# 4Wheel_MotorDrivers_Encoders.net
KiCad netlist of a schematic drawn in Altium Designer
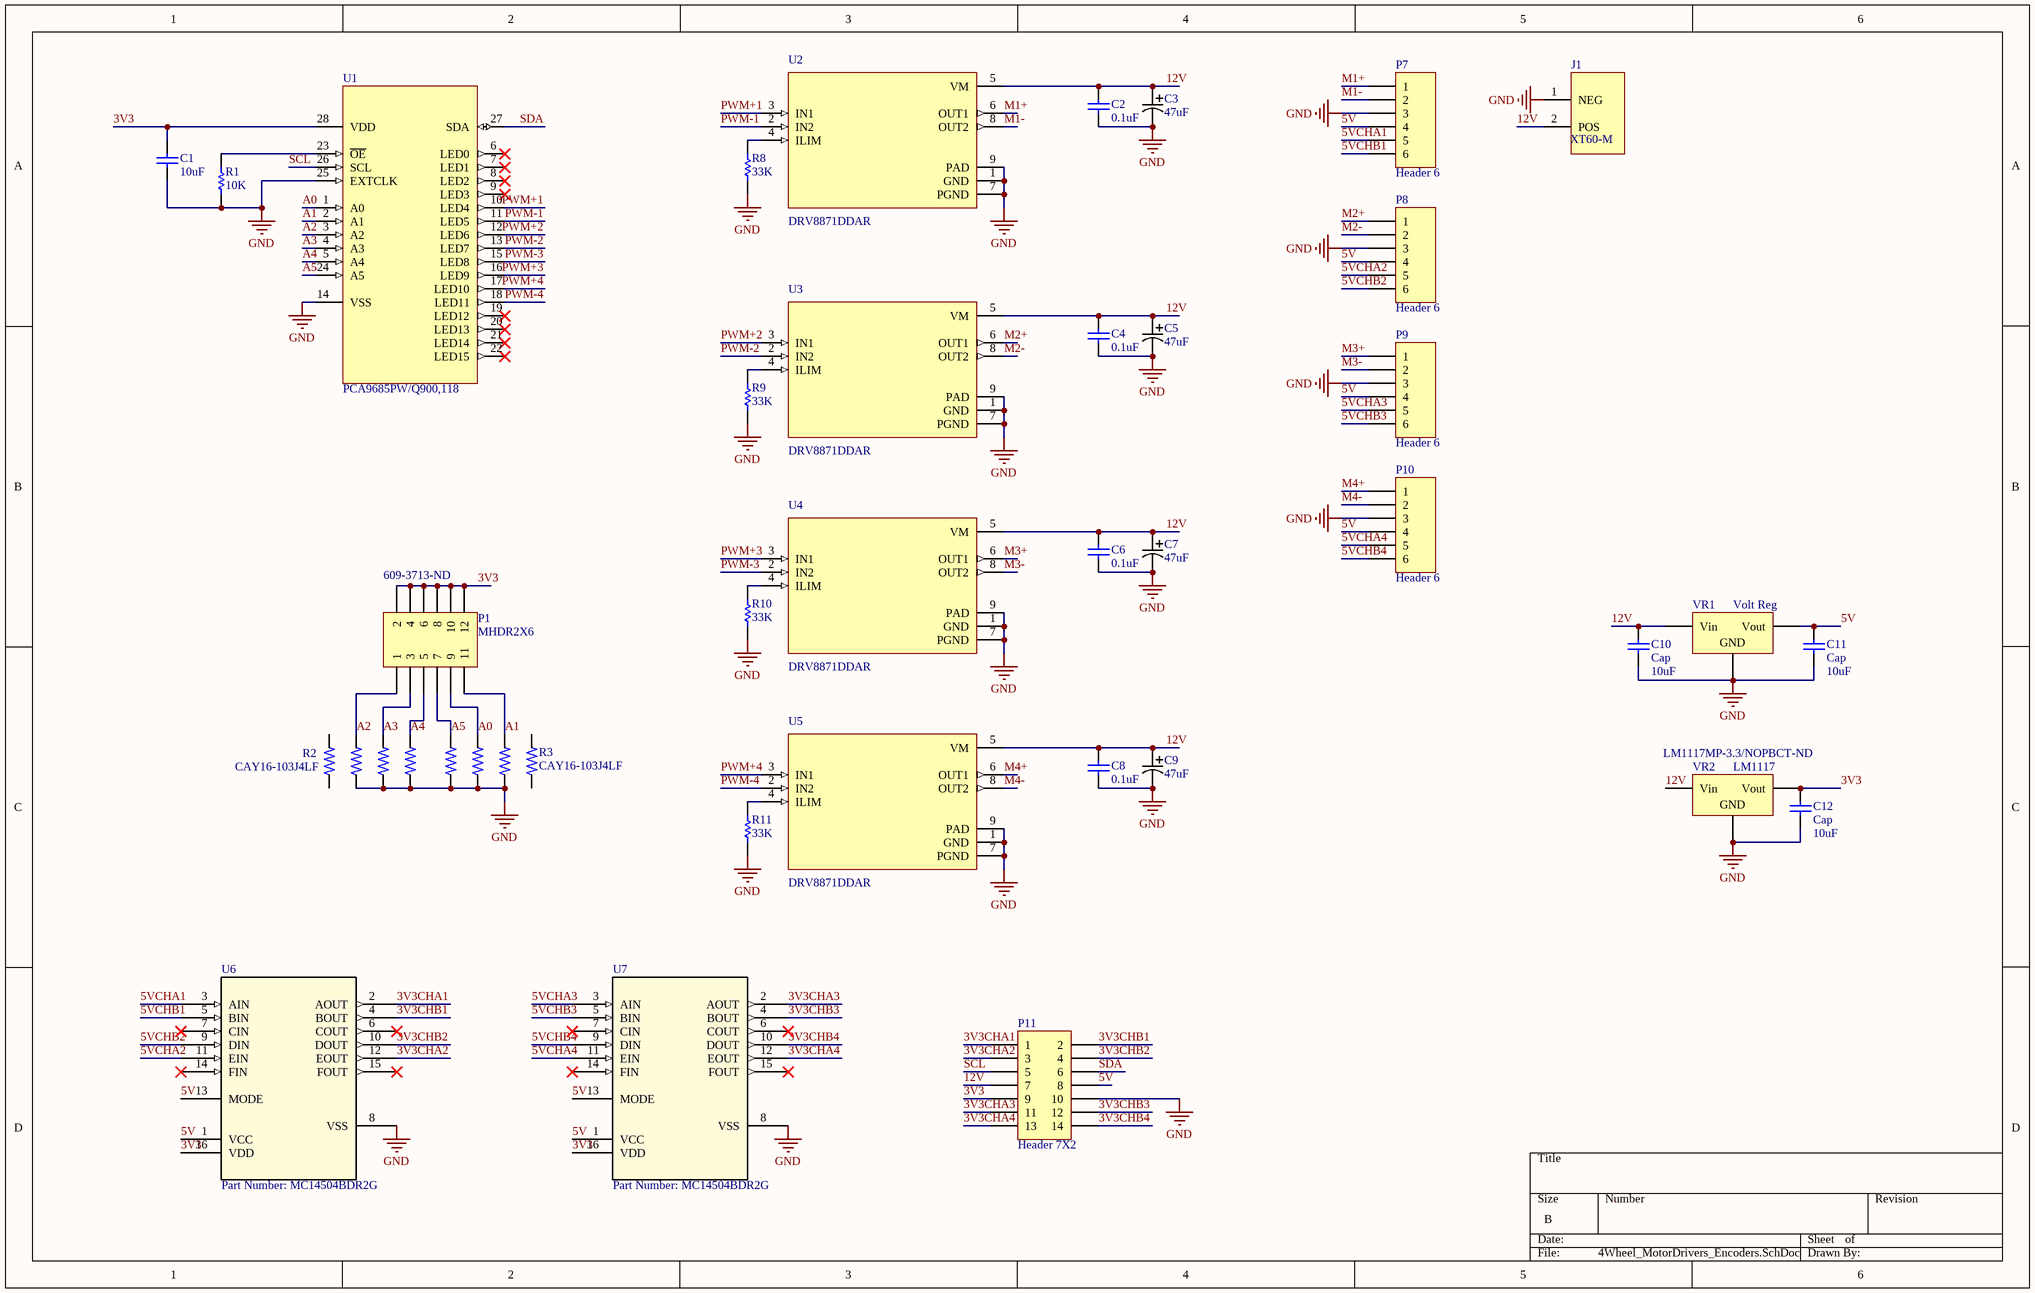
[diagram p0: 4Wheel_MotorDrivers_Encoders.SchDoc]

(export (version "E")
  (design (tool "Eeschema 10.0.6"))
  (components
    (comp (ref "C1")
      (value "10uF")
      (footprint "6-0805_N")
      (description "Capacitor")
      (fields (field (name "Comment") "Cap") (field (name "PUBLISHER") "Altium Limited"))
      (libsource (lib "Miscellaneous Devices") (part "Cap"))
    )
    (comp (ref "C2")
      (value "0.1uF")
      (footprint "6-0805_N")
      (description "Capacitor")
      (fields (field (name "PUBLISHER") "Altium Limited"))
      (libsource (lib "Miscellaneous Devices") (part "Cap"))
    )
    (comp (ref "C3")
      (value "47uF")
      (footprint "PCAP_6.3x7.7-ELE")
      (description "No Description Available")
      (fields
        (field (name "MANUFACTURER_PART_NUMBER") "UWT1H470MCL1GS")
        (field (name "COPYRIGHT") "Copyright (C) 2018 Accelerated Designs. All rights reserved")
      )
      (libsource (lib "2020-02-13_23-38-10") (part "UWT1H470MCL1GS"))
    )
    (comp (ref "C4")
      (value "0.1uF")
      (footprint "6-0805_N")
      (description "Capacitor")
      (fields (field (name "PUBLISHER") "Altium Limited"))
      (libsource (lib "Miscellaneous Devices") (part "Cap"))
    )
    (comp (ref "C5")
      (value "47uF")
      (footprint "PCAP_6.3x7.7-ELE")
      (description "No Description Available")
      (fields
        (field (name "MANUFACTURER_PART_NUMBER") "UWT1H470MCL1GS")
        (field (name "COPYRIGHT") "Copyright (C) 2018 Accelerated Designs. All rights reserved")
      )
      (libsource (lib "2020-02-13_23-38-10") (part "UWT1H470MCL1GS"))
    )
    (comp (ref "C6")
      (value "0.1uF")
      (footprint "6-0805_N")
      (description "Capacitor")
      (fields (field (name "PUBLISHER") "Altium Limited"))
      (libsource (lib "Miscellaneous Devices") (part "Cap"))
    )
    (comp (ref "C7")
      (value "47uF")
      (footprint "PCAP_6.3x7.7-ELE")
      (description "No Description Available")
      (fields
        (field (name "MANUFACTURER_PART_NUMBER") "UWT1H470MCL1GS")
        (field (name "COPYRIGHT") "Copyright (C) 2018 Accelerated Designs. All rights reserved")
      )
      (libsource (lib "2020-02-13_23-38-10") (part "UWT1H470MCL1GS"))
    )
    (comp (ref "C8")
      (value "0.1uF")
      (footprint "6-0805_N")
      (description "Capacitor")
      (fields (field (name "PUBLISHER") "Altium Limited"))
      (libsource (lib "Miscellaneous Devices") (part "Cap"))
    )
    (comp (ref "C9")
      (value "47uF")
      (footprint "PCAP_6.3x7.7-ELE")
      (description "No Description Available")
      (fields
        (field (name "MANUFACTURER_PART_NUMBER") "UWT1H470MCL1GS")
        (field (name "COPYRIGHT") "Copyright (C) 2018 Accelerated Designs. All rights reserved")
      )
      (libsource (lib "2020-02-13_23-38-10") (part "UWT1H470MCL1GS"))
    )
    (comp (ref "C10")
      (value "Cap")
      (footprint "6-0805_N")
      (description "Capacitor")
      (fields (field (name "ALTIUM_VALUE") "10uF") (field (name "PUBLISHER") "Altium Limited"))
      (libsource (lib "Miscellaneous Devices") (part "Cap"))
    )
    (comp (ref "C11")
      (value "Cap")
      (footprint "6-0805_N")
      (description "Capacitor")
      (fields (field (name "ALTIUM_VALUE") "10uF") (field (name "PUBLISHER") "Altium Limited"))
      (libsource (lib "Miscellaneous Devices") (part "Cap"))
    )
    (comp (ref "C12")
      (value "Cap")
      (footprint "6-0805_N")
      (description "Capacitor")
      (fields (field (name "ALTIUM_VALUE") "10uF") (field (name "PUBLISHER") "Altium Limited"))
      (libsource (lib "Miscellaneous Devices") (part "Cap"))
    )
    (comp (ref "J1")
      (value "XT60-M")
      (footprint "*AMASS_XT60-M")
      (description "Plug; DC supply; XT60; male; PIN: 2; for cable; soldered; 30A; 500V")
      (fields (field (name "MF") "AMASS"))
      (libsource (lib "XT60-M") (part "XT60-M"))
    )
    (comp (ref "P1")
      (value "MHDR2X6")
      (footprint "MHDR2X6")
      (description "Header, 6-Pin, Dual row")
      (fields
        (field (name "SUPPLIER PART NUMBER 1") "609-3713-ND")
        (field (name "PUBLISHER") "Altium Limited")
      )
      (libsource (lib "Miscellaneous Connectors") (part "MHDR2X6"))
    )
    (comp (ref "P7")
      (value "Header 6")
      (footprint "HDR1X6")
      (description "Header, 6-Pin")
      (fields (field (name "PUBLISHER") "Altium Limited"))
      (libsource (lib "Miscellaneous Connectors") (part "Header 6"))
    )
    (comp (ref "P8")
      (value "Header 6")
      (footprint "HDR1X6")
      (description "Header, 6-Pin")
      (fields (field (name "PUBLISHER") "Altium Limited"))
      (libsource (lib "Miscellaneous Connectors") (part "Header 6"))
    )
    (comp (ref "P9")
      (value "Header 6")
      (footprint "HDR1X6")
      (description "Header, 6-Pin")
      (fields (field (name "PUBLISHER") "Altium Limited"))
      (libsource (lib "Miscellaneous Connectors") (part "Header 6"))
    )
    (comp (ref "P10")
      (value "Header 6")
      (footprint "HDR1X6")
      (description "Header, 6-Pin")
      (fields (field (name "PUBLISHER") "Altium Limited"))
      (libsource (lib "Miscellaneous Connectors") (part "Header 6"))
    )
    (comp (ref "P11")
      (value "Header 7X2")
      (footprint "HDR1X14")
      (description "Header, 7-Pin, Dual row")
      (fields (field (name "PUBLISHER") "Altium Limited"))
      (libsource (lib "Miscellaneous Connectors") (part "Header 7X2"))
    )
    (comp (ref "R1")
      (value "10K")
      (footprint "6-0805_N")
      (description "Resistor")
      (fields (field (name "Comment") "Res1") (field (name "PUBLISHER") "Altium Limited"))
      (libsource (lib "Miscellaneous Devices") (part "Res1"))
    )
    (comp (ref "R2")
      (value "CAY16-103J4LF")
      (footprint "CAY16-J4")
      (fields (field (name "MF") "Bourns"))
      (libsource (lib "CAY16-103J4LF") (part "CAY16-103J4LF"))
    )
    (comp (ref "R3")
      (value "CAY16-103J4LF")
      (footprint "CAY16-J4")
      (fields (field (name "MF") "Bourns"))
      (libsource (lib "CAY16-103J4LF") (part "CAY16-103J4LF"))
    )
    (comp (ref "R8")
      (value "33K")
      (footprint "6-0805_N")
      (description "Resistor")
      (fields (field (name "Comment") "Res1") (field (name "PUBLISHER") "Altium Limited"))
      (libsource (lib "Miscellaneous Devices") (part "Res1"))
    )
    (comp (ref "R9")
      (value "33K")
      (footprint "6-0805_N")
      (description "Resistor")
      (fields (field (name "Comment") "Res1") (field (name "PUBLISHER") "Altium Limited"))
      (libsource (lib "Miscellaneous Devices") (part "Res1"))
    )
    (comp (ref "R10")
      (value "33K")
      (footprint "6-0805_N")
      (description "Resistor")
      (fields (field (name "Comment") "Res1") (field (name "PUBLISHER") "Altium Limited"))
      (libsource (lib "Miscellaneous Devices") (part "Res1"))
    )
    (comp (ref "R11")
      (value "33K")
      (footprint "6-0805_N")
      (description "Resistor")
      (fields (field (name "Comment") "Res1") (field (name "PUBLISHER") "Altium Limited"))
      (libsource (lib "Miscellaneous Devices") (part "Res1"))
    )
    (comp (ref "U1")
      (value "PCA9685PW/Q900,118")
      (footprint "*SOP65P640X110-28N")
      (description "LED Driver IC 16 Output Linear PWM Dimming 25mA 28-TSSOP")
      (fields (field (name "MF") "NXP USA") (field (name "DIGI-KEY_PART_NUMBER") "568-5931-1-ND"))
      (libsource (lib "PCA9685PW_Q900_118") (part "PCA9685PW/Q900,118"))
    )
    (comp (ref "U2")
      (value "DRV8871DDAR")
      (footprint "*SOIC127P600X170-8N")
      (description "Unipolar Motor Driver NMOS PWM 8-SO PowerPad")
      (fields (field (name "DIGI-KEY_PART_NUMBER") "296-43024-1-ND") (field (name "MF") "Texas Instruments"))
      (libsource (lib "DRV8871DDAR") (part "DRV8871DDAR"))
    )
    (comp (ref "U3")
      (value "DRV8871DDAR")
      (footprint "*SOIC127P600X170-8N")
      (description "Unipolar Motor Driver NMOS PWM 8-SO PowerPad")
      (fields (field (name "DIGI-KEY_PART_NUMBER") "296-43024-1-ND") (field (name "MF") "Texas Instruments"))
      (libsource (lib "DRV8871DDAR") (part "DRV8871DDAR"))
    )
    (comp (ref "U4")
      (value "DRV8871DDAR")
      (footprint "*SOIC127P600X170-8N")
      (description "Unipolar Motor Driver NMOS PWM 8-SO PowerPad")
      (fields (field (name "DIGI-KEY_PART_NUMBER") "296-43024-1-ND") (field (name "MF") "Texas Instruments"))
      (libsource (lib "DRV8871DDAR") (part "DRV8871DDAR"))
    )
    (comp (ref "U5")
      (value "DRV8871DDAR")
      (footprint "*SOIC127P600X170-8N")
      (description "Unipolar Motor Driver NMOS PWM 8-SO PowerPad")
      (fields (field (name "DIGI-KEY_PART_NUMBER") "296-43024-1-ND") (field (name "MF") "Texas Instruments"))
      (libsource (lib "DRV8871DDAR") (part "DRV8871DDAR"))
    )
    (comp (ref "U6")
      (value "Part Number: MC14504BDR2G")
      (footprint "SOIC-16")
      (description "No Description Available")
      (fields
        (field (name "MANUFACTURER_PART_NUMBER") "MC14504BDR2G")
        (field (name "COPYRIGHT") "Copyright (C) 2016 Accelerated Designs. All rights reserved")
      )
      (libsource (lib "2020-02-13_23-03-03") (part "MC14504BDR2G"))
    )
    (comp (ref "U7")
      (value "Part Number: MC14504BDR2G")
      (footprint "SOIC-16")
      (description "No Description Available")
      (fields
        (field (name "MANUFACTURER_PART_NUMBER") "MC14504BDR2G")
        (field (name "COPYRIGHT") "Copyright (C) 2016 Accelerated Designs. All rights reserved")
      )
      (libsource (lib "2020-02-13_23-03-03") (part "MC14504BDR2G"))
    )
    (comp (ref "VR1")
      (value "Volt Reg")
      (footprint "*TO254P1524X483-4N")
      (description "Voltage Regulator")
      (fields (field (name "PUBLISHER") "Altium Limited"))
      (libsource (lib "Miscellaneous Devices") (part "Volt Reg"))
    )
    (comp (ref "VR2")
      (value "LM1117")
      (footprint "SOT223_L")
      (description "Voltage Regulator")
      (fields
        (field (name "SUPPLIER PART NUMBER 1") "LM1117MP-3.3/NOPBCT-ND")
        (field (name "PUBLISHER") "Altium Limited")
      )
      (libsource (lib "Miscellaneous Devices") (part "Volt Reg"))
    )
  )
  (nets
    (net (code "1") (name "/3V3") (class "Default")
      (node (ref "C1") (pin "2") (pinfunction "2_2") (pintype "passive"))
      (node (ref "C12") (pin "2") (pinfunction "2_2") (pintype "passive"))
      (node (ref "P1") (pin "10") (pinfunction "10_10") (pintype "passive"))
      (node (ref "P1") (pin "12") (pinfunction "12_12") (pintype "passive"))
      (node (ref "P1") (pin "2") (pinfunction "2_2") (pintype "passive"))
      (node (ref "P1") (pin "4") (pinfunction "4_4") (pintype "passive"))
      (node (ref "P1") (pin "6") (pinfunction "6_6") (pintype "passive"))
      (node (ref "P1") (pin "8") (pinfunction "8_8") (pintype "passive"))
      (node (ref "P11") (pin "9") (pinfunction "9_9") (pintype "passive"))
      (node (ref "U1") (pin "28") (pinfunction "VDD_28") (pintype "power_in"))
      (node (ref "U6") (pin "16") (pinfunction "VDD_16") (pintype "power_in"))
      (node (ref "U7") (pin "16") (pinfunction "VDD_16") (pintype "power_in"))
      (node (ref "VR2") (pin "3") (pinfunction "Vout_3") (pintype "passive"))
    )
    (net (code "2") (name "/3V3CHA1") (class "Default")
      (node (ref "P11") (pin "1") (pinfunction "1_1") (pintype "passive"))
      (node (ref "U6") (pin "2") (pinfunction "AOUT_2") (pintype "output"))
    )
    (net (code "3") (name "/3V3CHA2") (class "Default")
      (node (ref "P11") (pin "3") (pinfunction "3_3") (pintype "passive"))
      (node (ref "U6") (pin "12") (pinfunction "EOUT_12") (pintype "output"))
    )
    (net (code "4") (name "/3V3CHA3") (class "Default")
      (node (ref "P11") (pin "11") (pinfunction "11_11") (pintype "passive"))
      (node (ref "U7") (pin "2") (pinfunction "AOUT_2") (pintype "output"))
    )
    (net (code "5") (name "/3V3CHA4") (class "Default")
      (node (ref "P11") (pin "13") (pinfunction "13_13") (pintype "passive"))
      (node (ref "U7") (pin "12") (pinfunction "EOUT_12") (pintype "output"))
    )
    (net (code "6") (name "/3V3CHB1") (class "Default")
      (node (ref "P11") (pin "2") (pinfunction "2_2") (pintype "passive"))
      (node (ref "U6") (pin "4") (pinfunction "BOUT_4") (pintype "output"))
    )
    (net (code "7") (name "/3V3CHB2") (class "Default")
      (node (ref "P11") (pin "4") (pinfunction "4_4") (pintype "passive"))
      (node (ref "U6") (pin "10") (pinfunction "DOUT_10") (pintype "output"))
    )
    (net (code "8") (name "/3V3CHB3") (class "Default")
      (node (ref "P11") (pin "12") (pinfunction "12_12") (pintype "passive"))
      (node (ref "U7") (pin "4") (pinfunction "BOUT_4") (pintype "output"))
    )
    (net (code "9") (name "/3V3CHB4") (class "Default")
      (node (ref "P11") (pin "14") (pinfunction "14_14") (pintype "passive"))
      (node (ref "U7") (pin "10") (pinfunction "DOUT_10") (pintype "output"))
    )
    (net (code "10") (name "/5V") (class "Default")
      (node (ref "C11") (pin "2") (pinfunction "2_2") (pintype "passive"))
      (node (ref "P10") (pin "4") (pinfunction "4_4") (pintype "passive"))
      (node (ref "P11") (pin "8") (pinfunction "8_8") (pintype "passive"))
      (node (ref "P7") (pin "4") (pinfunction "4_4") (pintype "passive"))
      (node (ref "P8") (pin "4") (pinfunction "4_4") (pintype "passive"))
      (node (ref "P9") (pin "4") (pinfunction "4_4") (pintype "passive"))
      (node (ref "U6") (pin "1") (pinfunction "VCC_1") (pintype "power_in"))
      (node (ref "U6") (pin "13") (pinfunction "MODE_13") (pintype "passive"))
      (node (ref "U7") (pin "1") (pinfunction "VCC_1") (pintype "power_in"))
      (node (ref "U7") (pin "13") (pinfunction "MODE_13") (pintype "passive"))
      (node (ref "VR1") (pin "3") (pinfunction "Vout_3") (pintype "passive"))
    )
    (net (code "11") (name "/5VCHA1") (class "Default")
      (node (ref "P7") (pin "5") (pinfunction "5_5") (pintype "passive"))
      (node (ref "U6") (pin "3") (pinfunction "AIN_3") (pintype "input"))
    )
    (net (code "12") (name "/5VCHA2") (class "Default")
      (node (ref "P8") (pin "5") (pinfunction "5_5") (pintype "passive"))
      (node (ref "U6") (pin "11") (pinfunction "EIN_11") (pintype "input"))
    )
    (net (code "13") (name "/5VCHA3") (class "Default")
      (node (ref "P9") (pin "5") (pinfunction "5_5") (pintype "passive"))
      (node (ref "U7") (pin "3") (pinfunction "AIN_3") (pintype "input"))
    )
    (net (code "14") (name "/5VCHA4") (class "Default")
      (node (ref "P10") (pin "5") (pinfunction "5_5") (pintype "passive"))
      (node (ref "U7") (pin "11") (pinfunction "EIN_11") (pintype "input"))
    )
    (net (code "15") (name "/5VCHB1") (class "Default")
      (node (ref "P7") (pin "6") (pinfunction "6_6") (pintype "passive"))
      (node (ref "U6") (pin "5") (pinfunction "BIN_5") (pintype "input"))
    )
    (net (code "16") (name "/5VCHB2") (class "Default")
      (node (ref "P8") (pin "6") (pinfunction "6_6") (pintype "passive"))
      (node (ref "U6") (pin "9") (pinfunction "DIN_9") (pintype "input"))
    )
    (net (code "17") (name "/5VCHB3") (class "Default")
      (node (ref "P9") (pin "6") (pinfunction "6_6") (pintype "passive"))
      (node (ref "U7") (pin "5") (pinfunction "BIN_5") (pintype "input"))
    )
    (net (code "18") (name "/5VCHB4") (class "Default")
      (node (ref "P10") (pin "6") (pinfunction "6_6") (pintype "passive"))
      (node (ref "U7") (pin "9") (pinfunction "DIN_9") (pintype "input"))
    )
    (net (code "19") (name "/12V") (class "Default")
      (node (ref "C10") (pin "2") (pinfunction "2_2") (pintype "passive"))
      (node (ref "C2") (pin "2") (pinfunction "2_2") (pintype "passive"))
      (node (ref "C3") (pin "1") (pinfunction "1_1") (pintype "passive"))
      (node (ref "C4") (pin "2") (pinfunction "2_2") (pintype "passive"))
      (node (ref "C5") (pin "1") (pinfunction "1_1") (pintype "passive"))
      (node (ref "C6") (pin "2") (pinfunction "2_2") (pintype "passive"))
      (node (ref "C7") (pin "1") (pinfunction "1_1") (pintype "passive"))
      (node (ref "C8") (pin "2") (pinfunction "2_2") (pintype "passive"))
      (node (ref "C9") (pin "1") (pinfunction "1_1") (pintype "passive"))
      (node (ref "J1") (pin "2") (pinfunction "POS_2") (pintype "passive"))
      (node (ref "P11") (pin "7") (pinfunction "7_7") (pintype "passive"))
      (node (ref "U2") (pin "5") (pinfunction "VM_5") (pintype "power_in"))
      (node (ref "U3") (pin "5") (pinfunction "VM_5") (pintype "power_in"))
      (node (ref "U4") (pin "5") (pinfunction "VM_5") (pintype "power_in"))
      (node (ref "U5") (pin "5") (pinfunction "VM_5") (pintype "power_in"))
      (node (ref "VR1") (pin "1") (pinfunction "Vin_1") (pintype "passive"))
      (node (ref "VR2") (pin "1") (pinfunction "Vin_1") (pintype "passive"))
    )
    (net (code "20") (name "/A0") (class "Default")
      (node (ref "P1") (pin "9") (pinfunction "9_9") (pintype "passive"))
      (node (ref "R3") (pin "7") (pinfunction "7_7") (pintype "passive"))
      (node (ref "U1") (pin "1") (pinfunction "A0_1") (pintype "input"))
    )
    (net (code "21") (name "/A1") (class "Default")
      (node (ref "P1") (pin "11") (pinfunction "11_11") (pintype "passive"))
      (node (ref "R3") (pin "6") (pinfunction "6_6") (pintype "passive"))
      (node (ref "U1") (pin "2") (pinfunction "A1_2") (pintype "input"))
    )
    (net (code "22") (name "/A2") (class "Default")
      (node (ref "P1") (pin "1") (pinfunction "1_1") (pintype "passive"))
      (node (ref "R2") (pin "7") (pinfunction "7_7") (pintype "passive"))
      (node (ref "U1") (pin "3") (pinfunction "A2_3") (pintype "input"))
    )
    (net (code "23") (name "/A3") (class "Default")
      (node (ref "P1") (pin "3") (pinfunction "3_3") (pintype "passive"))
      (node (ref "R2") (pin "6") (pinfunction "6_6") (pintype "passive"))
      (node (ref "U1") (pin "4") (pinfunction "A3_4") (pintype "input"))
    )
    (net (code "24") (name "/A4") (class "Default")
      (node (ref "P1") (pin "5") (pinfunction "5_5") (pintype "passive"))
      (node (ref "R2") (pin "5") (pinfunction "5_5") (pintype "passive"))
      (node (ref "U1") (pin "5") (pinfunction "A4_5") (pintype "input"))
    )
    (net (code "25") (name "/A5") (class "Default")
      (node (ref "P1") (pin "7") (pinfunction "7_7") (pintype "passive"))
      (node (ref "R3") (pin "8") (pinfunction "8_8") (pintype "passive"))
      (node (ref "U1") (pin "24") (pinfunction "A5_24") (pintype "input"))
    )
    (net (code "26") (name "/M1+") (class "Default")
      (node (ref "P7") (pin "1") (pinfunction "1_1") (pintype "passive"))
      (node (ref "U2") (pin "6") (pinfunction "OUT1_6") (pintype "output"))
    )
    (net (code "27") (name "/M1-") (class "Default")
      (node (ref "P7") (pin "2") (pinfunction "2_2") (pintype "passive"))
      (node (ref "U2") (pin "8") (pinfunction "OUT2_8") (pintype "output"))
    )
    (net (code "28") (name "/M2+") (class "Default")
      (node (ref "P8") (pin "1") (pinfunction "1_1") (pintype "passive"))
      (node (ref "U3") (pin "6") (pinfunction "OUT1_6") (pintype "output"))
    )
    (net (code "29") (name "/M2-") (class "Default")
      (node (ref "P8") (pin "2") (pinfunction "2_2") (pintype "passive"))
      (node (ref "U3") (pin "8") (pinfunction "OUT2_8") (pintype "output"))
    )
    (net (code "30") (name "/M3+") (class "Default")
      (node (ref "P9") (pin "1") (pinfunction "1_1") (pintype "passive"))
      (node (ref "U4") (pin "6") (pinfunction "OUT1_6") (pintype "output"))
    )
    (net (code "31") (name "/M3-") (class "Default")
      (node (ref "P9") (pin "2") (pinfunction "2_2") (pintype "passive"))
      (node (ref "U4") (pin "8") (pinfunction "OUT2_8") (pintype "output"))
    )
    (net (code "32") (name "/M4+") (class "Default")
      (node (ref "P10") (pin "1") (pinfunction "1_1") (pintype "passive"))
      (node (ref "U5") (pin "6") (pinfunction "OUT1_6") (pintype "output"))
    )
    (net (code "33") (name "/M4-") (class "Default")
      (node (ref "P10") (pin "2") (pinfunction "2_2") (pintype "passive"))
      (node (ref "U5") (pin "8") (pinfunction "OUT2_8") (pintype "output"))
    )
    (net (code "34") (name "/PWM+1") (class "Default")
      (node (ref "U1") (pin "10") (pinfunction "LED4_10") (pintype "output"))
      (node (ref "U2") (pin "3") (pinfunction "IN1_3") (pintype "input"))
    )
    (net (code "35") (name "/PWM+2") (class "Default")
      (node (ref "U1") (pin "12") (pinfunction "LED6_12") (pintype "output"))
      (node (ref "U3") (pin "3") (pinfunction "IN1_3") (pintype "input"))
    )
    (net (code "36") (name "/PWM+3") (class "Default")
      (node (ref "U1") (pin "16") (pinfunction "LED9_16") (pintype "output"))
      (node (ref "U4") (pin "3") (pinfunction "IN1_3") (pintype "input"))
    )
    (net (code "37") (name "/PWM+4") (class "Default")
      (node (ref "U1") (pin "17") (pinfunction "LED10_17") (pintype "output"))
      (node (ref "U5") (pin "3") (pinfunction "IN1_3") (pintype "input"))
    )
    (net (code "38") (name "/PWM-1") (class "Default")
      (node (ref "U1") (pin "11") (pinfunction "LED5_11") (pintype "output"))
      (node (ref "U2") (pin "2") (pinfunction "IN2_2") (pintype "input"))
    )
    (net (code "39") (name "/PWM-2") (class "Default")
      (node (ref "U1") (pin "13") (pinfunction "LED7_13") (pintype "output"))
      (node (ref "U3") (pin "2") (pinfunction "IN2_2") (pintype "input"))
    )
    (net (code "40") (name "/PWM-3") (class "Default")
      (node (ref "U1") (pin "15") (pinfunction "LED8_15") (pintype "output"))
      (node (ref "U4") (pin "2") (pinfunction "IN2_2") (pintype "input"))
    )
    (net (code "41") (name "/PWM-4") (class "Default")
      (node (ref "U1") (pin "18") (pinfunction "LED11_18") (pintype "output"))
      (node (ref "U5") (pin "2") (pinfunction "IN2_2") (pintype "input"))
    )
    (net (code "42") (name "/SCL") (class "Default")
      (node (ref "P11") (pin "5") (pinfunction "5_5") (pintype "passive"))
      (node (ref "U1") (pin "26") (pinfunction "SCL_26") (pintype "input"))
    )
    (net (code "43") (name "/SDA") (class "Default")
      (node (ref "P11") (pin "6") (pinfunction "6_6") (pintype "passive"))
      (node (ref "U1") (pin "27") (pinfunction "SDA_27") (pintype "bidirectional"))
    )
    (net (code "44") (name "GND") (class "Default")
      (node (ref "C1") (pin "1") (pinfunction "1_1") (pintype "passive"))
      (node (ref "C10") (pin "1") (pinfunction "1_1") (pintype "passive"))
      (node (ref "C11") (pin "1") (pinfunction "1_1") (pintype "passive"))
      (node (ref "C12") (pin "1") (pinfunction "1_1") (pintype "passive"))
      (node (ref "C2") (pin "1") (pinfunction "1_1") (pintype "passive"))
      (node (ref "C3") (pin "2") (pinfunction "2_2") (pintype "passive"))
      (node (ref "C4") (pin "1") (pinfunction "1_1") (pintype "passive"))
      (node (ref "C5") (pin "2") (pinfunction "2_2") (pintype "passive"))
      (node (ref "C6") (pin "1") (pinfunction "1_1") (pintype "passive"))
      (node (ref "C7") (pin "2") (pinfunction "2_2") (pintype "passive"))
      (node (ref "C8") (pin "1") (pinfunction "1_1") (pintype "passive"))
      (node (ref "C9") (pin "2") (pinfunction "2_2") (pintype "passive"))
      (node (ref "J1") (pin "1") (pinfunction "NEG_1") (pintype "passive"))
      (node (ref "P10") (pin "3") (pinfunction "3_3") (pintype "passive"))
      (node (ref "P11") (pin "10") (pinfunction "10_10") (pintype "passive"))
      (node (ref "P7") (pin "3") (pinfunction "3_3") (pintype "passive"))
      (node (ref "P8") (pin "3") (pinfunction "3_3") (pintype "passive"))
      (node (ref "P9") (pin "3") (pinfunction "3_3") (pintype "passive"))
      (node (ref "R1") (pin "1") (pinfunction "1_1") (pintype "passive"))
      (node (ref "R10") (pin "1") (pinfunction "1_1") (pintype "passive"))
      (node (ref "R11") (pin "1") (pinfunction "1_1") (pintype "passive"))
      (node (ref "R2") (pin "2") (pinfunction "2_2") (pintype "passive"))
      (node (ref "R2") (pin "3") (pinfunction "3_3") (pintype "passive"))
      (node (ref "R2") (pin "4") (pinfunction "4_4") (pintype "passive"))
      (node (ref "R3") (pin "1") (pinfunction "1_1") (pintype "passive"))
      (node (ref "R3") (pin "2") (pinfunction "2_2") (pintype "passive"))
      (node (ref "R3") (pin "3") (pinfunction "3_3") (pintype "passive"))
      (node (ref "R8") (pin "1") (pinfunction "1_1") (pintype "passive"))
      (node (ref "R9") (pin "1") (pinfunction "1_1") (pintype "passive"))
      (node (ref "U1") (pin "14") (pinfunction "VSS_14") (pintype "passive"))
      (node (ref "U1") (pin "25") (pinfunction "EXTCLK_25") (pintype "input"))
      (node (ref "U2") (pin "1") (pinfunction "GND_1") (pintype "power_in"))
      (node (ref "U2") (pin "7") (pinfunction "PGND_7") (pintype "power_in"))
      (node (ref "U2") (pin "9") (pinfunction "PAD_9") (pintype "power_in"))
      (node (ref "U3") (pin "1") (pinfunction "GND_1") (pintype "power_in"))
      (node (ref "U3") (pin "7") (pinfunction "PGND_7") (pintype "power_in"))
      (node (ref "U3") (pin "9") (pinfunction "PAD_9") (pintype "power_in"))
      (node (ref "U4") (pin "1") (pinfunction "GND_1") (pintype "power_in"))
      (node (ref "U4") (pin "7") (pinfunction "PGND_7") (pintype "power_in"))
      (node (ref "U4") (pin "9") (pinfunction "PAD_9") (pintype "power_in"))
      (node (ref "U5") (pin "1") (pinfunction "GND_1") (pintype "power_in"))
      (node (ref "U5") (pin "7") (pinfunction "PGND_7") (pintype "power_in"))
      (node (ref "U5") (pin "9") (pinfunction "PAD_9") (pintype "power_in"))
      (node (ref "U6") (pin "8") (pinfunction "VSS_8") (pintype "power_in"))
      (node (ref "U7") (pin "8") (pinfunction "VSS_8") (pintype "power_in"))
      (node (ref "VR1") (pin "2") (pinfunction "GND_2") (pintype "passive"))
      (node (ref "VR2") (pin "2") (pinfunction "GND_2") (pintype "passive"))
    )
    (net (code "45") (name "Net-(U1-~{OE})") (class "Default")
      (node (ref "R1") (pin "2") (pinfunction "2_2") (pintype "passive"))
      (node (ref "U1") (pin "23") (pinfunction "~{OE}_23") (pintype "input"))
    )
    (net (code "46") (name "Net-(U2-ILIM)") (class "Default")
      (node (ref "R8") (pin "2") (pinfunction "2_2") (pintype "passive"))
      (node (ref "U2") (pin "4") (pinfunction "ILIM_4") (pintype "input"))
    )
    (net (code "47") (name "Net-(U3-ILIM)") (class "Default")
      (node (ref "R9") (pin "2") (pinfunction "2_2") (pintype "passive"))
      (node (ref "U3") (pin "4") (pinfunction "ILIM_4") (pintype "input"))
    )
    (net (code "48") (name "Net-(U4-ILIM)") (class "Default")
      (node (ref "R10") (pin "2") (pinfunction "2_2") (pintype "passive"))
      (node (ref "U4") (pin "4") (pinfunction "ILIM_4") (pintype "input"))
    )
    (net (code "49") (name "Net-(U5-ILIM)") (class "Default")
      (node (ref "R11") (pin "2") (pinfunction "2_2") (pintype "passive"))
      (node (ref "U5") (pin "4") (pinfunction "ILIM_4") (pintype "input"))
    )
    (net (code "50") (name "unconnected-(R2-Pad1)") (class "Default")
      (node (ref "R2") (pin "1") (pinfunction "1_1") (pintype "passive"))
    )
    (net (code "51") (name "unconnected-(R2-Pad8)") (class "Default")
      (node (ref "R2") (pin "8") (pinfunction "8_8") (pintype "passive"))
    )
    (net (code "52") (name "unconnected-(R3-Pad4)") (class "Default")
      (node (ref "R3") (pin "4") (pinfunction "4_4") (pintype "passive"))
    )
    (net (code "53") (name "unconnected-(R3-Pad5)") (class "Default")
      (node (ref "R3") (pin "5") (pinfunction "5_5") (pintype "passive"))
    )
    (net (code "54") (name "unconnected-(U1-LED0-Pad6)") (class "Default")
      (node (ref "U1") (pin "6") (pinfunction "LED0_6") (pintype "output+no_connect"))
    )
    (net (code "55") (name "unconnected-(U1-LED1-Pad7)") (class "Default")
      (node (ref "U1") (pin "7") (pinfunction "LED1_7") (pintype "output+no_connect"))
    )
    (net (code "56") (name "unconnected-(U1-LED2-Pad8)") (class "Default")
      (node (ref "U1") (pin "8") (pinfunction "LED2_8") (pintype "output+no_connect"))
    )
    (net (code "57") (name "unconnected-(U1-LED3-Pad9)") (class "Default")
      (node (ref "U1") (pin "9") (pinfunction "LED3_9") (pintype "output+no_connect"))
    )
    (net (code "58") (name "unconnected-(U1-LED12-Pad19)") (class "Default")
      (node (ref "U1") (pin "19") (pinfunction "LED12_19") (pintype "output+no_connect"))
    )
    (net (code "59") (name "unconnected-(U1-LED13-Pad20)") (class "Default")
      (node (ref "U1") (pin "20") (pinfunction "LED13_20") (pintype "output+no_connect"))
    )
    (net (code "60") (name "unconnected-(U1-LED14-Pad21)") (class "Default")
      (node (ref "U1") (pin "21") (pinfunction "LED14_21") (pintype "output+no_connect"))
    )
    (net (code "61") (name "unconnected-(U1-LED15-Pad22)") (class "Default")
      (node (ref "U1") (pin "22") (pinfunction "LED15_22") (pintype "output+no_connect"))
    )
    (net (code "62") (name "unconnected-(U6-CIN-Pad7)") (class "Default")
      (node (ref "U6") (pin "7") (pinfunction "CIN_7") (pintype "input+no_connect"))
    )
    (net (code "63") (name "unconnected-(U6-COUT-Pad6)") (class "Default")
      (node (ref "U6") (pin "6") (pinfunction "COUT_6") (pintype "output+no_connect"))
    )
    (net (code "64") (name "unconnected-(U6-FIN-Pad14)") (class "Default")
      (node (ref "U6") (pin "14") (pinfunction "FIN_14") (pintype "input+no_connect"))
    )
    (net (code "65") (name "unconnected-(U6-FOUT-Pad15)") (class "Default")
      (node (ref "U6") (pin "15") (pinfunction "FOUT_15") (pintype "output+no_connect"))
    )
    (net (code "66") (name "unconnected-(U7-CIN-Pad7)") (class "Default")
      (node (ref "U7") (pin "7") (pinfunction "CIN_7") (pintype "input+no_connect"))
    )
    (net (code "67") (name "unconnected-(U7-COUT-Pad6)") (class "Default")
      (node (ref "U7") (pin "6") (pinfunction "COUT_6") (pintype "output+no_connect"))
    )
    (net (code "68") (name "unconnected-(U7-FIN-Pad14)") (class "Default")
      (node (ref "U7") (pin "14") (pinfunction "FIN_14") (pintype "input+no_connect"))
    )
    (net (code "69") (name "unconnected-(U7-FOUT-Pad15)") (class "Default")
      (node (ref "U7") (pin "15") (pinfunction "FOUT_15") (pintype "output+no_connect"))
    )
  )
)
